# aruduino-shield.net
KiCad netlist of a schematic drawn in EAGLE
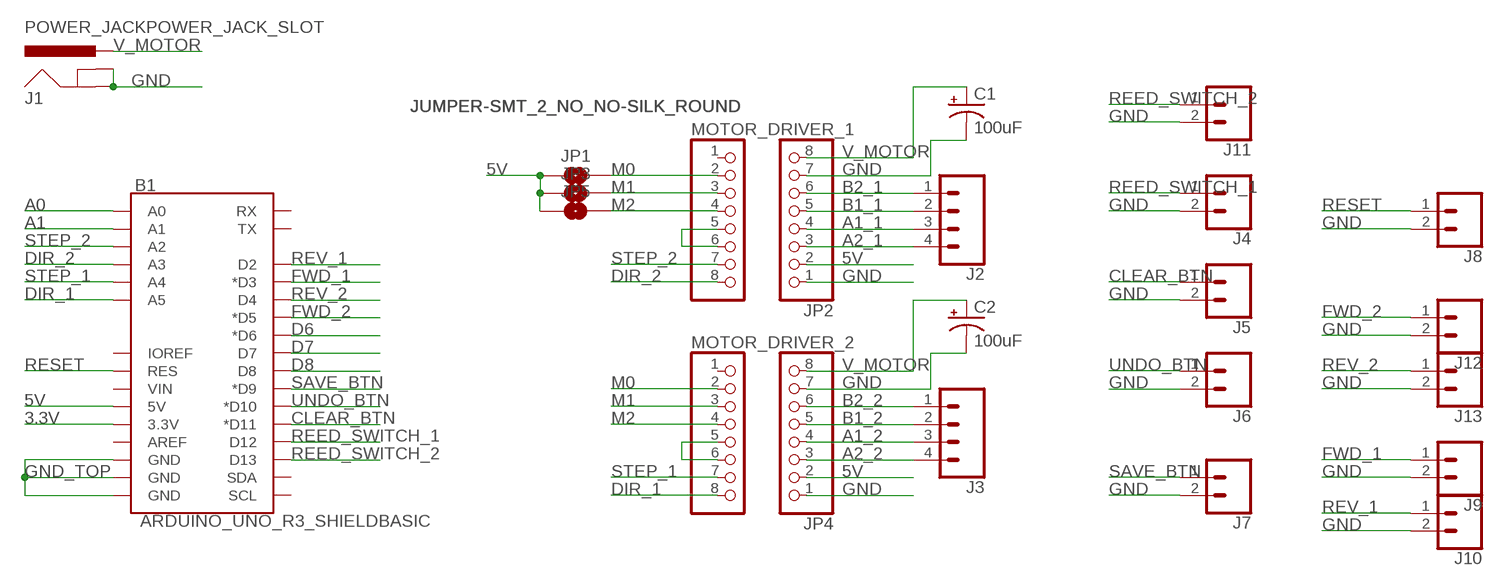
[diagram p0: schematic, sheet 1]

(export (version "E")
  (design (tool "Eeschema 10.0.6"))
  (components
    (comp (ref "B1")
      (value "ARDUINO_UNO_R3_SHIELDBASIC")
      (footprint "eagle-import:UNO_R3_SHIELD")
      (libsource (lib "eagle-import") (part "ARDUINO_UNO_R3_SHIELDBASIC"))
    )
    (comp (ref "C1")
      (value "100uF")
      (footprint "eagle-import:CPOL-RADIAL-2.5MM-6.5MM")
      (libsource (lib "eagle-import") (part "100UF-POLAR-RADIAL-2.5MM-25V-20%"))
    )
    (comp (ref "C2")
      (value "100uF")
      (footprint "eagle-import:CPOL-RADIAL-2.5MM-6.5MM")
      (libsource (lib "eagle-import") (part "100UF-POLAR-RADIAL-2.5MM-25V-20%"))
    )
    (comp (ref "J1")
      (value "POWER_JACKPOWER_JACK_SLOT")
      (footprint "eagle-import:POWER_JACK_PTH_SLOT")
      (libsource (lib "eagle-import") (part "POWER_JACKPOWER_JACK_SLOT"))
    )
    (comp (ref "J2")
      (value "CONN_04SCREW")
      (footprint "eagle-import:SCREWTERMINAL-3.5MM-4")
      (libsource (lib "eagle-import") (part "CONN_04SCREW"))
    )
    (comp (ref "J3")
      (value "CONN_04SCREW")
      (footprint "eagle-import:SCREWTERMINAL-3.5MM-4")
      (libsource (lib "eagle-import") (part "CONN_04SCREW"))
    )
    (comp (ref "J4")
      (value "CONN_02")
      (footprint "eagle-import:1X02")
      (libsource (lib "eagle-import") (part "CONN_02"))
    )
    (comp (ref "J5")
      (value "CONN_02")
      (footprint "eagle-import:1X02")
      (libsource (lib "eagle-import") (part "CONN_02"))
    )
    (comp (ref "J6")
      (value "CONN_02")
      (footprint "eagle-import:1X02")
      (libsource (lib "eagle-import") (part "CONN_02"))
    )
    (comp (ref "J7")
      (value "CONN_02")
      (footprint "eagle-import:1X02")
      (libsource (lib "eagle-import") (part "CONN_02"))
    )
    (comp (ref "J8")
      (value "CONN_02")
      (footprint "eagle-import:1X02")
      (libsource (lib "eagle-import") (part "CONN_02"))
    )
    (comp (ref "J9")
      (value "CONN_02")
      (footprint "eagle-import:1X02")
      (libsource (lib "eagle-import") (part "CONN_02"))
    )
    (comp (ref "J10")
      (value "CONN_02")
      (footprint "eagle-import:1X02")
      (libsource (lib "eagle-import") (part "CONN_02"))
    )
    (comp (ref "J11")
      (value "CONN_02")
      (footprint "eagle-import:1X02")
      (libsource (lib "eagle-import") (part "CONN_02"))
    )
    (comp (ref "J12")
      (value "CONN_02")
      (footprint "eagle-import:1X02")
      (libsource (lib "eagle-import") (part "CONN_02"))
    )
    (comp (ref "J13")
      (value "CONN_02")
      (footprint "eagle-import:1X02")
      (libsource (lib "eagle-import") (part "CONN_02"))
    )
    (comp (ref "JP1")
      (value "JUMPER-SMT_2_NO_NO-SILK_ROUND")
      (footprint "eagle-import:SMT-JUMPER_2_NO_NO-SILK_ROUND")
      (libsource (lib "eagle-import") (part "JUMPER-SMT_2_NO_NO-SILK_ROUND"))
    )
    (comp (ref "JP2")
      (value "PINHD-1X8CLEANBIG")
      (footprint "eagle-import:1X08-CLEANBIG")
      (libsource (lib "eagle-import") (part "PINHD-1X8CLEANBIG"))
    )
    (comp (ref "JP3")
      (value "JUMPER-SMT_2_NO_NO-SILK_ROUND")
      (footprint "eagle-import:SMT-JUMPER_2_NO_NO-SILK_ROUND")
      (libsource (lib "eagle-import") (part "JUMPER-SMT_2_NO_NO-SILK_ROUND"))
    )
    (comp (ref "JP4")
      (value "PINHD-1X8CLEANBIG")
      (footprint "eagle-import:1X08-CLEANBIG")
      (libsource (lib "eagle-import") (part "PINHD-1X8CLEANBIG"))
    )
    (comp (ref "JP5")
      (value "JUMPER-SMT_2_NO_NO-SILK_ROUND")
      (footprint "eagle-import:SMT-JUMPER_2_NO_NO-SILK_ROUND")
      (libsource (lib "eagle-import") (part "JUMPER-SMT_2_NO_NO-SILK_ROUND"))
    )
    (comp (ref "MOTOR_DRIVER_1")
      (value "PINHD-1X8CLEANBIG")
      (footprint "eagle-import:1X08-CLEANBIG")
      (libsource (lib "eagle-import") (part "PINHD-1X8CLEANBIG"))
    )
    (comp (ref "MOTOR_DRIVER_2")
      (value "PINHD-1X8CLEANBIG")
      (footprint "eagle-import:1X08-CLEANBIG")
      (libsource (lib "eagle-import") (part "PINHD-1X8CLEANBIG"))
    )
  )
  (nets
    (net (code "1") (name "/3.3V") (class "Default")
      (node (ref "B1") (pin "3.3V") (pinfunction "3.3V_3.3V") (pintype "bidirectional"))
    )
    (net (code "2") (name "/5V") (class "Default")
      (node (ref "B1") (pin "5V") (pinfunction "5V_5V") (pintype "bidirectional"))
      (node (ref "JP1") (pin "1") (pinfunction "1_1") (pintype "passive"))
      (node (ref "JP2") (pin "2") (pinfunction "2_2") (pintype "passive"))
      (node (ref "JP3") (pin "1") (pinfunction "1_1") (pintype "passive"))
      (node (ref "JP4") (pin "2") (pinfunction "2_2") (pintype "passive"))
      (node (ref "JP5") (pin "1") (pinfunction "1_1") (pintype "passive"))
    )
    (net (code "3") (name "/A0") (class "Default")
      (node (ref "B1") (pin "A0") (pinfunction "A0_A0") (pintype "bidirectional"))
    )
    (net (code "4") (name "/A1") (class "Default")
      (node (ref "B1") (pin "A1") (pinfunction "A1_A1") (pintype "bidirectional"))
    )
    (net (code "5") (name "/A1_1") (class "Default")
      (node (ref "J2") (pin "3") (pinfunction "3_3") (pintype "passive"))
      (node (ref "JP2") (pin "4") (pinfunction "4_4") (pintype "passive"))
    )
    (net (code "6") (name "/A1_2") (class "Default")
      (node (ref "J3") (pin "3") (pinfunction "3_3") (pintype "passive"))
      (node (ref "JP4") (pin "4") (pinfunction "4_4") (pintype "passive"))
    )
    (net (code "7") (name "/A2_1") (class "Default")
      (node (ref "J2") (pin "4") (pinfunction "4_4") (pintype "passive"))
      (node (ref "JP2") (pin "3") (pinfunction "3_3") (pintype "passive"))
    )
    (net (code "8") (name "/A2_2") (class "Default")
      (node (ref "J3") (pin "4") (pinfunction "4_4") (pintype "passive"))
      (node (ref "JP4") (pin "3") (pinfunction "3_3") (pintype "passive"))
    )
    (net (code "9") (name "/B1_1") (class "Default")
      (node (ref "J2") (pin "2") (pinfunction "2_2") (pintype "passive"))
      (node (ref "JP2") (pin "5") (pinfunction "5_5") (pintype "passive"))
    )
    (net (code "10") (name "/B1_2") (class "Default")
      (node (ref "J3") (pin "2") (pinfunction "2_2") (pintype "passive"))
      (node (ref "JP4") (pin "5") (pinfunction "5_5") (pintype "passive"))
    )
    (net (code "11") (name "/B2_1") (class "Default")
      (node (ref "J2") (pin "1") (pinfunction "1_1") (pintype "passive"))
      (node (ref "JP2") (pin "6") (pinfunction "6_6") (pintype "passive"))
    )
    (net (code "12") (name "/B2_2") (class "Default")
      (node (ref "J3") (pin "1") (pinfunction "1_1") (pintype "passive"))
      (node (ref "JP4") (pin "6") (pinfunction "6_6") (pintype "passive"))
    )
    (net (code "13") (name "/CLEAR_BTN") (class "Default")
      (node (ref "B1") (pin "D11") (pinfunction "*D11_D11") (pintype "bidirectional"))
      (node (ref "J5") (pin "1") (pinfunction "1_1") (pintype "passive"))
    )
    (net (code "14") (name "/D6") (class "Default")
      (node (ref "B1") (pin "D6") (pinfunction "*D6_D6") (pintype "bidirectional"))
    )
    (net (code "15") (name "/D7") (class "Default")
      (node (ref "B1") (pin "D7") (pinfunction "D7_D7") (pintype "bidirectional"))
    )
    (net (code "16") (name "/D8") (class "Default")
      (node (ref "B1") (pin "D8") (pinfunction "D8_D8") (pintype "bidirectional"))
    )
    (net (code "17") (name "/DIR_1") (class "Default")
      (node (ref "B1") (pin "A5") (pinfunction "A5_A5") (pintype "bidirectional"))
      (node (ref "MOTOR_DRIVER_2") (pin "8") (pinfunction "8_8") (pintype "passive"))
    )
    (net (code "18") (name "/DIR_2") (class "Default")
      (node (ref "B1") (pin "A3") (pinfunction "A3_A3") (pintype "bidirectional"))
      (node (ref "MOTOR_DRIVER_1") (pin "8") (pinfunction "8_8") (pintype "passive"))
    )
    (net (code "19") (name "/FWD_1") (class "Default")
      (node (ref "B1") (pin "D3") (pinfunction "*D3_D3") (pintype "bidirectional"))
      (node (ref "J9") (pin "1") (pinfunction "1_1") (pintype "passive"))
    )
    (net (code "20") (name "/FWD_2") (class "Default")
      (node (ref "B1") (pin "D5") (pinfunction "*D5_D5") (pintype "bidirectional"))
      (node (ref "J12") (pin "1") (pinfunction "1_1") (pintype "passive"))
    )
    (net (code "21") (name "/GND") (class "Default")
      (node (ref "C1") (pin "2") (pinfunction "-_2") (pintype "passive"))
      (node (ref "C2") (pin "2") (pinfunction "-_2") (pintype "passive"))
      (node (ref "J1") (pin "GND") (pinfunction "GND_GND") (pintype "bidirectional"))
      (node (ref "J1") (pin "GNDBREAK") (pinfunction "GNDBREAK_GNDBREAK") (pintype "bidirectional"))
      (node (ref "J10") (pin "2") (pinfunction "2_2") (pintype "passive"))
      (node (ref "J11") (pin "2") (pinfunction "2_2") (pintype "passive"))
      (node (ref "J12") (pin "2") (pinfunction "2_2") (pintype "passive"))
      (node (ref "J13") (pin "2") (pinfunction "2_2") (pintype "passive"))
      (node (ref "J4") (pin "2") (pinfunction "2_2") (pintype "passive"))
      (node (ref "J5") (pin "2") (pinfunction "2_2") (pintype "passive"))
      (node (ref "J6") (pin "2") (pinfunction "2_2") (pintype "passive"))
      (node (ref "J7") (pin "2") (pinfunction "2_2") (pintype "passive"))
      (node (ref "J8") (pin "2") (pinfunction "2_2") (pintype "passive"))
      (node (ref "J9") (pin "2") (pinfunction "2_2") (pintype "passive"))
      (node (ref "JP2") (pin "1") (pinfunction "1_1") (pintype "passive"))
      (node (ref "JP2") (pin "7") (pinfunction "7_7") (pintype "passive"))
      (node (ref "JP4") (pin "1") (pinfunction "1_1") (pintype "passive"))
      (node (ref "JP4") (pin "7") (pinfunction "7_7") (pintype "passive"))
    )
    (net (code "22") (name "/GND_TOP") (class "Default")
      (node (ref "B1") (pin "GND@0") (pinfunction "GND_GND@0") (pintype "bidirectional"))
      (node (ref "B1") (pin "GND@1") (pinfunction "GND_GND@1") (pintype "bidirectional"))
      (node (ref "B1") (pin "GND@2") (pinfunction "GND_GND@2") (pintype "bidirectional"))
    )
    (net (code "23") (name "/M0") (class "Default")
      (node (ref "JP1") (pin "2") (pinfunction "2_2") (pintype "passive"))
      (node (ref "MOTOR_DRIVER_1") (pin "2") (pinfunction "2_2") (pintype "passive"))
      (node (ref "MOTOR_DRIVER_2") (pin "2") (pinfunction "2_2") (pintype "passive"))
    )
    (net (code "24") (name "/M1") (class "Default")
      (node (ref "JP3") (pin "2") (pinfunction "2_2") (pintype "passive"))
      (node (ref "MOTOR_DRIVER_1") (pin "3") (pinfunction "3_3") (pintype "passive"))
      (node (ref "MOTOR_DRIVER_2") (pin "3") (pinfunction "3_3") (pintype "passive"))
    )
    (net (code "25") (name "/M2") (class "Default")
      (node (ref "JP5") (pin "2") (pinfunction "2_2") (pintype "passive"))
      (node (ref "MOTOR_DRIVER_1") (pin "4") (pinfunction "4_4") (pintype "passive"))
      (node (ref "MOTOR_DRIVER_2") (pin "4") (pinfunction "4_4") (pintype "passive"))
    )
    (net (code "26") (name "/REED_SWITCH_1") (class "Default")
      (node (ref "B1") (pin "D12") (pinfunction "D12_D12") (pintype "bidirectional"))
      (node (ref "J4") (pin "1") (pinfunction "1_1") (pintype "passive"))
    )
    (net (code "27") (name "/REED_SWITCH_2") (class "Default")
      (node (ref "B1") (pin "D13") (pinfunction "D13_D13") (pintype "bidirectional"))
      (node (ref "J11") (pin "1") (pinfunction "1_1") (pintype "passive"))
    )
    (net (code "28") (name "/RESET") (class "Default")
      (node (ref "B1") (pin "RES") (pinfunction "RES_RES") (pintype "bidirectional"))
      (node (ref "J8") (pin "1") (pinfunction "1_1") (pintype "passive"))
    )
    (net (code "29") (name "/REV_1") (class "Default")
      (node (ref "B1") (pin "D2") (pinfunction "D2_D2") (pintype "bidirectional"))
      (node (ref "J10") (pin "1") (pinfunction "1_1") (pintype "passive"))
    )
    (net (code "30") (name "/REV_2") (class "Default")
      (node (ref "B1") (pin "D4") (pinfunction "D4_D4") (pintype "bidirectional"))
      (node (ref "J13") (pin "1") (pinfunction "1_1") (pintype "passive"))
    )
    (net (code "31") (name "/SAVE_BTN") (class "Default")
      (node (ref "B1") (pin "D9") (pinfunction "*D9_D9") (pintype "bidirectional"))
      (node (ref "J7") (pin "1") (pinfunction "1_1") (pintype "passive"))
    )
    (net (code "32") (name "/STEP_1") (class "Default")
      (node (ref "B1") (pin "A4") (pinfunction "A4_A4") (pintype "bidirectional"))
      (node (ref "MOTOR_DRIVER_2") (pin "7") (pinfunction "7_7") (pintype "passive"))
    )
    (net (code "33") (name "/STEP_2") (class "Default")
      (node (ref "B1") (pin "A2") (pinfunction "A2_A2") (pintype "bidirectional"))
      (node (ref "MOTOR_DRIVER_1") (pin "7") (pinfunction "7_7") (pintype "passive"))
    )
    (net (code "34") (name "/UNDO_BTN") (class "Default")
      (node (ref "B1") (pin "D10") (pinfunction "*D10_D10") (pintype "bidirectional"))
      (node (ref "J6") (pin "1") (pinfunction "1_1") (pintype "passive"))
    )
    (net (code "35") (name "/V_MOTOR") (class "Default")
      (node (ref "C1") (pin "1") (pinfunction "+_1") (pintype "passive"))
      (node (ref "C2") (pin "1") (pinfunction "+_1") (pintype "passive"))
      (node (ref "J1") (pin "PWR") (pinfunction "PWR_PWR") (pintype "bidirectional"))
      (node (ref "JP2") (pin "8") (pinfunction "8_8") (pintype "passive"))
      (node (ref "JP4") (pin "8") (pinfunction "8_8") (pintype "passive"))
    )
    (net (code "36") (name "Net-(MOTOR_DRIVER_1-Pad5)") (class "Default")
      (node (ref "MOTOR_DRIVER_1") (pin "5") (pinfunction "5_5") (pintype "passive"))
      (node (ref "MOTOR_DRIVER_1") (pin "6") (pinfunction "6_6") (pintype "passive"))
    )
    (net (code "37") (name "Net-(MOTOR_DRIVER_2-Pad5)") (class "Default")
      (node (ref "MOTOR_DRIVER_2") (pin "5") (pinfunction "5_5") (pintype "passive"))
      (node (ref "MOTOR_DRIVER_2") (pin "6") (pinfunction "6_6") (pintype "passive"))
    )
    (net (code "38") (name "unconnected-(B1-PadAREF)") (class "Default")
      (node (ref "B1") (pin "AREF") (pinfunction "AREF_AREF") (pintype "bidirectional"))
    )
    (net (code "39") (name "unconnected-(B1-PadIOREF)") (class "Default")
      (node (ref "B1") (pin "IOREF") (pinfunction "IOREF_IOREF") (pintype "bidirectional"))
    )
    (net (code "40") (name "unconnected-(B1-PadRX)") (class "Default")
      (node (ref "B1") (pin "RX") (pinfunction "RX_RX") (pintype "bidirectional"))
    )
    (net (code "41") (name "unconnected-(B1-PadSCL)") (class "Default")
      (node (ref "B1") (pin "SCL") (pinfunction "SCL_SCL") (pintype "bidirectional"))
    )
    (net (code "42") (name "unconnected-(B1-PadSDA)") (class "Default")
      (node (ref "B1") (pin "SDA") (pinfunction "SDA_SDA") (pintype "bidirectional"))
    )
    (net (code "43") (name "unconnected-(B1-PadTX)") (class "Default")
      (node (ref "B1") (pin "TX") (pinfunction "TX_TX") (pintype "bidirectional"))
    )
    (net (code "44") (name "unconnected-(B1-PadVIN)") (class "Default")
      (node (ref "B1") (pin "VIN") (pinfunction "VIN_VIN") (pintype "bidirectional"))
    )
    (net (code "45") (name "unconnected-(MOTOR_DRIVER_1-Pad1)") (class "Default")
      (node (ref "MOTOR_DRIVER_1") (pin "1") (pinfunction "1_1") (pintype "passive"))
    )
    (net (code "46") (name "unconnected-(MOTOR_DRIVER_2-Pad1)") (class "Default")
      (node (ref "MOTOR_DRIVER_2") (pin "1") (pinfunction "1_1") (pintype "passive"))
    )
  )
)
